# MCU_board_2.net
KiCad netlist of a schematic drawn in Altium Designer
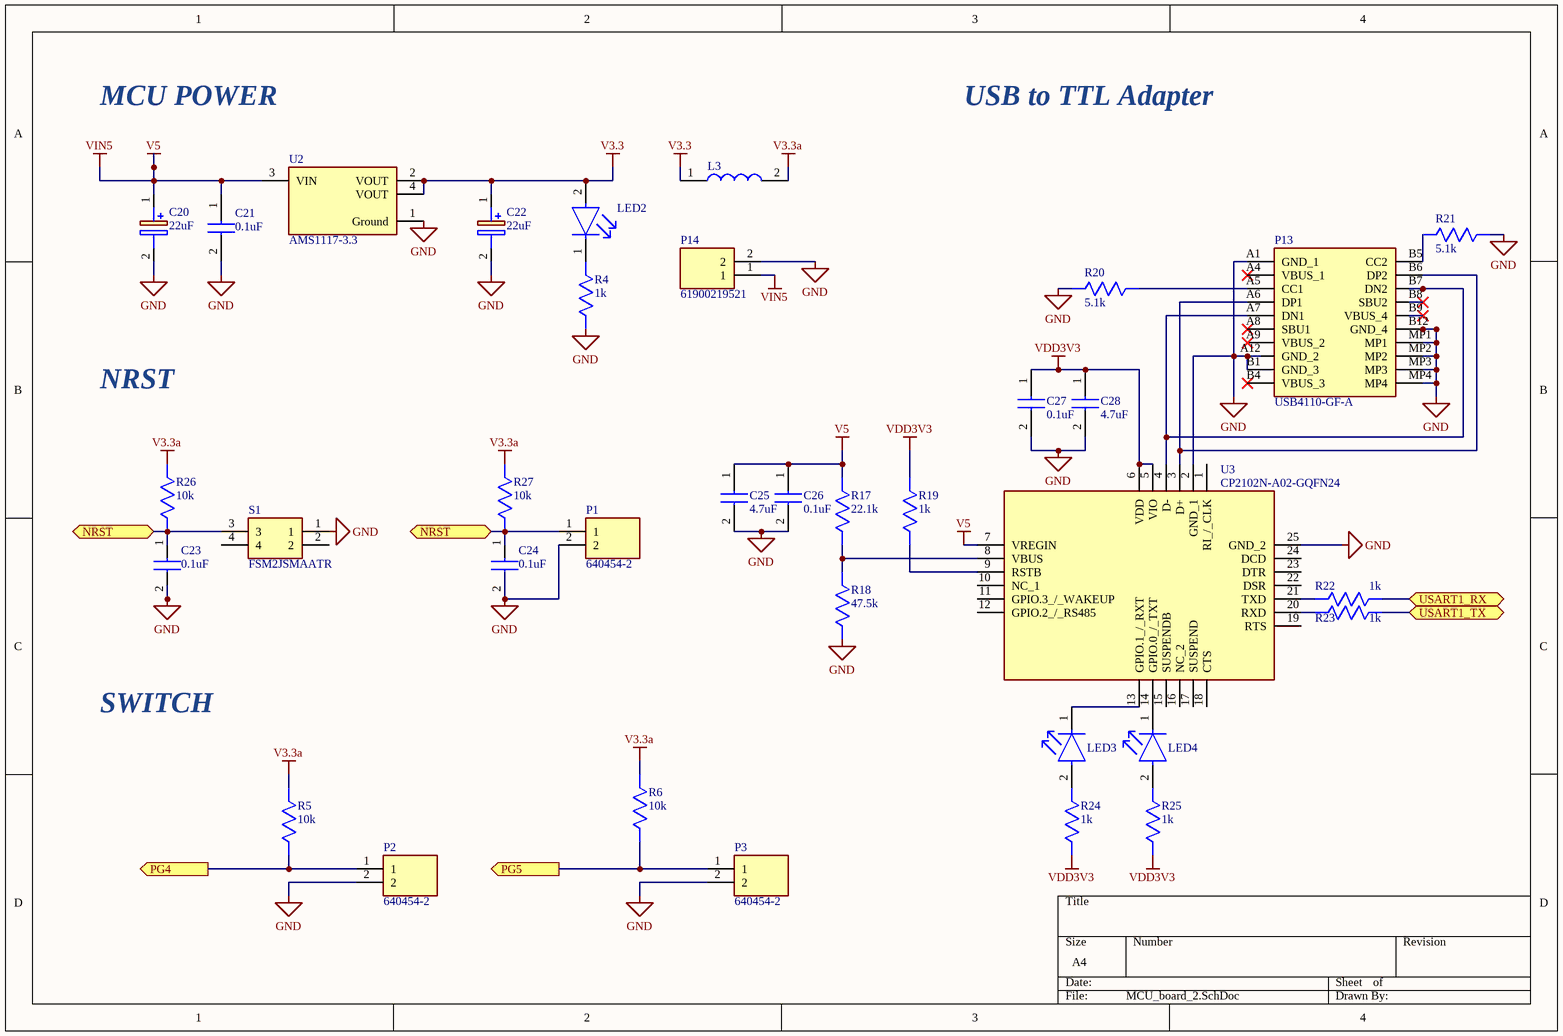
[diagram p0: MCU_board_2.SchDoc]

(export (version "E")
  (design (tool "Eeschema 10.0.6"))
  (components
    (comp (ref "C20")
      (value "22uF")
      (footprint "SamacSys:CAPPM6032X280N")
      (description "Capacitor Polarised")
      (fields
        (field (name "MANUFACTURER_PART_NUMBER") "TAJC226K025RNJ")
        (field (name "MOUSER PART NUMBER") "581-TAJC226K025R")
      )
      (libsource (lib "*") (part "TAJC226K025RNJ"))
    )
    (comp (ref "C21")
      (value "0.1uF")
      (footprint "SamacSys:C1608_Commercial")
      (description "Capacitor")
      (fields
        (field (name "MANUFACTURER_PART_NUMBER") "C1608X7R1H334K080AC")
        (field (name "MOUSER PART NUMBER") "810-C1608X7R1H334K")
      )
      (libsource (lib "*") (part "C1608X7R1H334K080AC"))
    )
    (comp (ref "C22")
      (value "22uF")
      (footprint "SamacSys:CAPPM6032X280N")
      (description "Capacitor Polarised")
      (fields
        (field (name "MANUFACTURER_PART_NUMBER") "TAJC226K025RNJ")
        (field (name "MOUSER PART NUMBER") "581-TAJC226K025R")
      )
      (libsource (lib "*") (part "TAJC226K025RNJ"))
    )
    (comp (ref "C23")
      (value "0.1uF")
      (footprint "SamacSys:C1608_Commercial")
      (description "Capacitor")
      (fields
        (field (name "MANUFACTURER_PART_NUMBER") "C1608X7R1H334K080AC")
        (field (name "MOUSER PART NUMBER") "810-C1608X7R1H334K")
      )
      (libsource (lib "*") (part "C1608X7R1H334K080AC"))
    )
    (comp (ref "C24")
      (value "0.1uF")
      (footprint "SamacSys:C1608_Commercial")
      (description "Capacitor")
      (fields
        (field (name "MANUFACTURER_PART_NUMBER") "C1608X7R1H334K080AC")
        (field (name "MOUSER PART NUMBER") "810-C1608X7R1H334K")
      )
      (libsource (lib "*") (part "C1608X7R1H334K080AC"))
    )
    (comp (ref "C25")
      (value "4.7uF")
      (footprint "SamacSys:CAPC1608X90N")
      (description "Capacitor")
      (fields
        (field (name "MANUFACTURER_PART_NUMBER") "GRM188R72A104MA35D")
        (field (name "MOUSER PART NUMBER") "81-GRM188R72A104MA5D")
      )
      (libsource (lib "*") (part "GRM188R72A104MA35D"))
    )
    (comp (ref "C26")
      (value "0.1uF")
      (footprint "SamacSys:CAPC1608X90N")
      (description "Capacitor")
      (fields
        (field (name "MANUFACTURER_PART_NUMBER") "GRM188R72A104MA35D")
        (field (name "MOUSER PART NUMBER") "81-GRM188R72A104MA5D")
      )
      (libsource (lib "*") (part "GRM188R72A104MA35D"))
    )
    (comp (ref "C27")
      (value "0.1uF")
      (footprint "SamacSys:CAPC1608X90N")
      (description "Capacitor")
      (fields
        (field (name "MANUFACTURER_PART_NUMBER") "GRM188R72A104MA35D")
        (field (name "MOUSER PART NUMBER") "81-GRM188R72A104MA5D")
      )
      (libsource (lib "*") (part "GRM188R72A104MA35D"))
    )
    (comp (ref "C28")
      (value "4.7uF")
      (footprint "SamacSys:CAPC1608X90N")
      (description "Capacitor")
      (fields
        (field (name "MANUFACTURER_PART_NUMBER") "GRM188R72A104MA35D")
        (field (name "MOUSER PART NUMBER") "81-GRM188R72A104MA5D")
      )
      (libsource (lib "*") (part "GRM188R72A104MA35D"))
    )
    (comp (ref "L3")
      (value "742792691")
      (footprint "SamacSys:LEDC1608X80N")
      (description "Inductor")
      (fields (field (name "MOUSER PART NUMBER") "710-742792691"))
      (libsource (lib "*") (part "742792691"))
    )
    (comp (ref "LED2")
      (value "150060RS75000")
      (footprint "FP-150060RS75000-MFG")
      (description "LED RED CLEAR 0603 SMD")
      (libsource (lib "Altium Content Vault") (part "8706943c75ba83719d021d2fdc84c58"))
    )
    (comp (ref "LED3")
      (value "150060RS75000")
      (footprint "FP-150060RS75000-MFG")
      (description "LED RED CLEAR 0603 SMD")
      (libsource (lib "Altium Content Vault") (part "8706943c75ba83719d021d2fdc84c58"))
    )
    (comp (ref "LED4")
      (value "150060RS75000")
      (footprint "FP-150060RS75000-MFG")
      (description "LED RED CLEAR 0603 SMD")
      (libsource (lib "Altium Content Vault") (part "8706943c75ba83719d021d2fdc84c58"))
    )
    (comp (ref "P1")
      (value "640454-2")
      (footprint "SamacSys:HDRV2W66P0X254_1X2_762X572X1003P")
      (description "Connector")
      (libsource (lib "*") (part "640454-2"))
    )
    (comp (ref "P2")
      (value "640454-2")
      (footprint "SamacSys:HDRV2W66P0X254_1X2_762X572X1003P")
      (description "Connector")
      (libsource (lib "SamacSys") (part "640454-2"))
    )
    (comp (ref "P3")
      (value "640454-2")
      (footprint "SamacSys:HDRV2W66P0X254_1X2_762X572X1003P")
      (description "Connector")
      (libsource (lib "SamacSys") (part "640454-2"))
    )
    (comp (ref "P13")
      (value "USB4110-GF-A")
      (footprint "SamacSys:USB4110GFA")
      (description "Connector")
      (fields (field (name "MOUSER PART NUMBER") "640-USB4110-GF-A"))
      (libsource (lib "SamacSys") (part "USB4110-GF-A"))
    )
    (comp (ref "P14")
      (value "61900219521")
      (footprint "SamacSys:SHDRRA2W64P0X254_1X2_508X1150X595P")
      (description "Connector")
      (fields (field (name "MOUSER PART NUMBER") "710-61900219521"))
      (libsource (lib "*") (part "61900219521"))
    )
    (comp (ref "R4")
      (value "1k")
      (footprint "SamacSys:RESC1608X55N")
      (description "Resistor")
      (fields (field (name "MANUFACTURER_PART_NUMBER") "CMP0603-FX-1003ELF"))
      (libsource (lib "SamacSys") (part "CMP0603-FX-1003ELF"))
    )
    (comp (ref "R5")
      (value "10k")
      (footprint "SamacSys:RESC1608X55N")
      (description "Resistor")
      (fields (field (name "MANUFACTURER_PART_NUMBER") "CMP0603-FX-1003ELF"))
      (libsource (lib "SamacSys") (part "CMP0603-FX-1003ELF"))
    )
    (comp (ref "R6")
      (value "10k")
      (footprint "SamacSys:RESC1608X55N")
      (description "Resistor")
      (fields (field (name "MANUFACTURER_PART_NUMBER") "CMP0603-FX-1003ELF"))
      (libsource (lib "SamacSys") (part "CMP0603-FX-1003ELF"))
    )
    (comp (ref "R17")
      (value "22.1k")
      (footprint "SamacSys:RESC1608X55N")
      (description "Resistor")
      (fields (field (name "MANUFACTURER_PART_NUMBER") "CMP0603-FX-1003ELF"))
      (libsource (lib "SamacSys") (part "CMP0603-FX-1003ELF"))
    )
    (comp (ref "R18")
      (value "47.5k")
      (footprint "SamacSys:RESC1608X55N")
      (description "Resistor")
      (fields (field (name "MANUFACTURER_PART_NUMBER") "CMP0603-FX-1003ELF"))
      (libsource (lib "SamacSys") (part "CMP0603-FX-1003ELF"))
    )
    (comp (ref "R19")
      (value "1k")
      (footprint "SamacSys:RESC1608X55N")
      (description "Resistor")
      (fields (field (name "MANUFACTURER_PART_NUMBER") "CMP0603-FX-1003ELF"))
      (libsource (lib "SamacSys") (part "CMP0603-FX-1003ELF"))
    )
    (comp (ref "R20")
      (value "5.1k")
      (footprint "SamacSys:RESC1608X55N")
      (description "Resistor")
      (fields (field (name "MANUFACTURER_PART_NUMBER") "CMP0603-FX-1003ELF"))
      (libsource (lib "SamacSys") (part "CMP0603-FX-1003ELF"))
    )
    (comp (ref "R21")
      (value "5.1k")
      (footprint "SamacSys:RESC1608X55N")
      (description "Resistor")
      (fields (field (name "MANUFACTURER_PART_NUMBER") "CMP0603-FX-1003ELF"))
      (libsource (lib "SamacSys") (part "CMP0603-FX-1003ELF"))
    )
    (comp (ref "R22")
      (value "1k")
      (footprint "SamacSys:RESC1608X55N")
      (description "Resistor")
      (fields (field (name "MANUFACTURER_PART_NUMBER") "CMP0603-FX-1003ELF"))
      (libsource (lib "SamacSys") (part "CMP0603-FX-1003ELF"))
    )
    (comp (ref "R23")
      (value "1k")
      (footprint "SamacSys:RESC1608X55N")
      (description "Resistor")
      (fields (field (name "MANUFACTURER_PART_NUMBER") "CMP0603-FX-1003ELF"))
      (libsource (lib "SamacSys") (part "CMP0603-FX-1003ELF"))
    )
    (comp (ref "R24")
      (value "1k")
      (footprint "SamacSys:RESC1608X55N")
      (description "Resistor")
      (fields (field (name "MANUFACTURER_PART_NUMBER") "CMP0603-FX-1003ELF"))
      (libsource (lib "SamacSys") (part "CMP0603-FX-1003ELF"))
    )
    (comp (ref "R25")
      (value "1k")
      (footprint "SamacSys:RESC1608X55N")
      (description "Resistor")
      (fields (field (name "MANUFACTURER_PART_NUMBER") "CMP0603-FX-1003ELF"))
      (libsource (lib "SamacSys") (part "CMP0603-FX-1003ELF"))
    )
    (comp (ref "R26")
      (value "10k")
      (footprint "SamacSys:RESC1608X55N")
      (description "Resistor")
      (fields (field (name "MANUFACTURER_PART_NUMBER") "CMP0603-FX-1003ELF"))
      (libsource (lib "SamacSys") (part "CMP0603-FX-1003ELF"))
    )
    (comp (ref "R27")
      (value "10k")
      (footprint "SamacSys:RESC1608X55N")
      (description "Resistor")
      (fields (field (name "MANUFACTURER_PART_NUMBER") "CMP0603-FX-1003ELF"))
      (libsource (lib "SamacSys") (part "CMP0603-FX-1003ELF"))
    )
    (comp (ref "S1")
      (value "FSM2JSMAATR")
      (footprint "SamacSys:FSM2J_1")
      (description "Switch")
      (libsource (lib "SamacSys") (part "FSM2JSMAATR"))
    )
    (comp (ref "U2")
      (value "AMS1117-3.3")
      (footprint "FP-AMS1117-IPC_C")
      (description "LDO Voltage Regulators 1A, 3.3V")
      (fields
        (field (name "OCTOPART") "https://octopart.com/ams1117-3.3-advanced+monolithic+systems-25899300")
        (field (name "MANUFACTURER") "Advanced Monolithic Systems")
      )
      (libsource (lib "Altium Content Vault") (part "8bdbb5f8e77002000e30dd2845d0354"))
    )
    (comp (ref "U3")
      (value "CP2102N-A02-GQFN24")
      (footprint "SamacSys:QFN50P400X400X80-25N-D")
      (description "Integrated Circuit")
      (fields (field (name "MOUSER PART NUMBER") "634-CP2102NA02GQFN24"))
      (libsource (lib "*") (part "CP2102N-A02-GQFN24"))
    )
  )
  (nets
    (net (code "1") (name "/NRST") (class "Default")
      (node (ref "C23") (pin "1") (pinfunction "1_1") (pintype "passive"))
      (node (ref "C24") (pin "1") (pinfunction "1_1") (pintype "passive"))
      (node (ref "P1") (pin "1") (pinfunction "1_1") (pintype "passive"))
      (node (ref "R26") (pin "1") (pinfunction "1_1") (pintype "passive"))
      (node (ref "R27") (pin "1") (pinfunction "1_1") (pintype "passive"))
      (node (ref "S1") (pin "3") (pinfunction "3_3") (pintype "passive"))
    )
    (net (code "2") (name "/PG4") (class "Default")
      (node (ref "P2") (pin "1") (pinfunction "1_1") (pintype "passive"))
      (node (ref "R5") (pin "1") (pinfunction "1_1") (pintype "passive"))
    )
    (net (code "3") (name "/PG5") (class "Default")
      (node (ref "P3") (pin "1") (pinfunction "1_1") (pintype "passive"))
      (node (ref "R6") (pin "1") (pinfunction "1_1") (pintype "passive"))
    )
    (net (code "4") (name "/USART1_RX") (class "Default")
      (node (ref "R22") (pin "2") (pinfunction "2_2") (pintype "passive"))
    )
    (net (code "5") (name "/USART1_TX") (class "Default")
      (node (ref "R23") (pin "2") (pinfunction "2_2") (pintype "passive"))
    )
    (net (code "6") (name "GND") (class "Default")
      (node (ref "C20") (pin "2") (pinfunction "-_2") (pintype "passive"))
      (node (ref "C21") (pin "2") (pinfunction "2_2") (pintype "passive"))
      (node (ref "C22") (pin "2") (pinfunction "-_2") (pintype "passive"))
      (node (ref "C23") (pin "2") (pinfunction "2_2") (pintype "passive"))
      (node (ref "C24") (pin "2") (pinfunction "2_2") (pintype "passive"))
      (node (ref "C25") (pin "2") (pinfunction "2_2") (pintype "passive"))
      (node (ref "C26") (pin "2") (pinfunction "2_2") (pintype "passive"))
      (node (ref "C27") (pin "2") (pinfunction "2_2") (pintype "passive"))
      (node (ref "C28") (pin "2") (pinfunction "2_2") (pintype "passive"))
      (node (ref "P1") (pin "2") (pinfunction "2_2") (pintype "passive"))
      (node (ref "P13") (pin "A1") (pinfunction "GND_1_A1") (pintype "passive"))
      (node (ref "P13") (pin "A12") (pinfunction "GND_2_A12") (pintype "passive"))
      (node (ref "P13") (pin "B1") (pinfunction "GND_3_B1") (pintype "passive"))
      (node (ref "P13") (pin "B12") (pinfunction "GND_4_B12") (pintype "passive"))
      (node (ref "P13") (pin "MP1") (pinfunction "MP1_MP1") (pintype "passive"))
      (node (ref "P13") (pin "MP2") (pinfunction "MP2_MP2") (pintype "passive"))
      (node (ref "P13") (pin "MP3") (pinfunction "MP3_MP3") (pintype "passive"))
      (node (ref "P13") (pin "MP4") (pinfunction "MP4_MP4") (pintype "passive"))
      (node (ref "P14") (pin "2") (pinfunction "2_2") (pintype "passive"))
      (node (ref "P2") (pin "2") (pinfunction "2_2") (pintype "passive"))
      (node (ref "P3") (pin "2") (pinfunction "2_2") (pintype "passive"))
      (node (ref "R18") (pin "2") (pinfunction "2_2") (pintype "passive"))
      (node (ref "R20") (pin "2") (pinfunction "2_2") (pintype "passive"))
      (node (ref "R21") (pin "2") (pinfunction "2_2") (pintype "passive"))
      (node (ref "R4") (pin "2") (pinfunction "2_2") (pintype "passive"))
      (node (ref "S1") (pin "1") (pinfunction "1_1") (pintype "passive"))
      (node (ref "U2") (pin "1") (pinfunction "Ground_1") (pintype "power_in"))
      (node (ref "U3") (pin "2") (pinfunction "GND_1_2") (pintype "passive"))
      (node (ref "U3") (pin "25") (pinfunction "GND_2_25") (pintype "passive"))
    )
    (net (code "7") (name "Net-(LED2-C)") (class "Default")
      (node (ref "LED2") (pin "1") (pinfunction "C_1") (pintype "passive"))
      (node (ref "R4") (pin "1") (pinfunction "1_1") (pintype "passive"))
    )
    (net (code "8") (name "Net-(LED3-A)") (class "Default")
      (node (ref "LED3") (pin "2") (pinfunction "A_2") (pintype "passive"))
      (node (ref "R24") (pin "1") (pinfunction "1_1") (pintype "passive"))
    )
    (net (code "9") (name "Net-(LED3-C)") (class "Default")
      (node (ref "LED3") (pin "1") (pinfunction "C_1") (pintype "passive"))
      (node (ref "U3") (pin "13") (pinfunction "GPIO.1_/_RXT_13") (pintype "passive"))
    )
    (net (code "10") (name "Net-(LED4-A)") (class "Default")
      (node (ref "LED4") (pin "2") (pinfunction "A_2") (pintype "passive"))
      (node (ref "R25") (pin "1") (pinfunction "1_1") (pintype "passive"))
    )
    (net (code "11") (name "Net-(LED4-C)") (class "Default")
      (node (ref "LED4") (pin "1") (pinfunction "C_1") (pintype "passive"))
      (node (ref "U3") (pin "14") (pinfunction "GPIO.0_/_TXT_14") (pintype "passive"))
    )
    (net (code "12") (name "Net-(P13-CC1)") (class "Default")
      (node (ref "P13") (pin "A5") (pinfunction "CC1_A5") (pintype "passive"))
      (node (ref "R20") (pin "1") (pinfunction "1_1") (pintype "passive"))
    )
    (net (code "13") (name "Net-(P13-CC2)") (class "Default")
      (node (ref "P13") (pin "B5") (pinfunction "CC2_B5") (pintype "passive"))
      (node (ref "R21") (pin "1") (pinfunction "1_1") (pintype "passive"))
    )
    (net (code "14") (name "Net-(P13-DN1)") (class "Default")
      (node (ref "P13") (pin "A7") (pinfunction "DN1_A7") (pintype "passive"))
      (node (ref "P13") (pin "B7") (pinfunction "DN2_B7") (pintype "passive"))
      (node (ref "U3") (pin "4") (pinfunction "D-_4") (pintype "passive"))
    )
    (net (code "15") (name "Net-(P13-DP1)") (class "Default")
      (node (ref "P13") (pin "A6") (pinfunction "DP1_A6") (pintype "passive"))
      (node (ref "P13") (pin "B6") (pinfunction "DP2_B6") (pintype "passive"))
      (node (ref "U3") (pin "3") (pinfunction "D+_3") (pintype "passive"))
    )
    (net (code "16") (name "Net-(U3-RSTB)") (class "Default")
      (node (ref "R19") (pin "2") (pinfunction "2_2") (pintype "passive"))
      (node (ref "U3") (pin "9") (pinfunction "RSTB_9") (pintype "passive"))
    )
    (net (code "17") (name "Net-(U3-RXD)") (class "Default")
      (node (ref "R23") (pin "1") (pinfunction "1_1") (pintype "passive"))
      (node (ref "U3") (pin "20") (pinfunction "RXD_20") (pintype "passive"))
    )
    (net (code "18") (name "Net-(U3-TXD)") (class "Default")
      (node (ref "R22") (pin "1") (pinfunction "1_1") (pintype "passive"))
      (node (ref "U3") (pin "21") (pinfunction "TXD_21") (pintype "passive"))
    )
    (net (code "19") (name "Net-(U3-VBUS)") (class "Default")
      (node (ref "R17") (pin "2") (pinfunction "2_2") (pintype "passive"))
      (node (ref "R18") (pin "1") (pinfunction "1_1") (pintype "passive"))
      (node (ref "U3") (pin "8") (pinfunction "VBUS_8") (pintype "passive"))
    )
    (net (code "20") (name "V3.3") (class "Default")
      (node (ref "C22") (pin "1") (pinfunction "+_1") (pintype "passive"))
      (node (ref "L3") (pin "1") (pinfunction "1_1") (pintype "passive"))
      (node (ref "LED2") (pin "2") (pinfunction "A_2") (pintype "passive"))
      (node (ref "U2") (pin "2") (pinfunction "VOUT_2") (pintype "passive"))
      (node (ref "U2") (pin "4") (pinfunction "VOUT_4") (pintype "passive"))
    )
    (net (code "21") (name "V3.3a") (class "Default")
      (node (ref "L3") (pin "2") (pinfunction "2_2") (pintype "passive"))
      (node (ref "R26") (pin "2") (pinfunction "2_2") (pintype "passive"))
      (node (ref "R27") (pin "2") (pinfunction "2_2") (pintype "passive"))
      (node (ref "R5") (pin "2") (pinfunction "2_2") (pintype "passive"))
      (node (ref "R6") (pin "2") (pinfunction "2_2") (pintype "passive"))
    )
    (net (code "22") (name "V5") (class "Default")
      (node (ref "C20") (pin "1") (pinfunction "+_1") (pintype "passive"))
      (node (ref "C21") (pin "1") (pinfunction "1_1") (pintype "passive"))
      (node (ref "C25") (pin "1") (pinfunction "1_1") (pintype "passive"))
      (node (ref "C26") (pin "1") (pinfunction "1_1") (pintype "passive"))
      (node (ref "P14") (pin "1") (pinfunction "1_1") (pintype "passive"))
      (node (ref "R17") (pin "1") (pinfunction "1_1") (pintype "passive"))
      (node (ref "U2") (pin "3") (pinfunction "VIN_3") (pintype "power_in"))
      (node (ref "U3") (pin "7") (pinfunction "VREGIN_7") (pintype "passive"))
    )
    (net (code "23") (name "VDD3V3") (class "Default")
      (node (ref "C27") (pin "1") (pinfunction "1_1") (pintype "passive"))
      (node (ref "C28") (pin "1") (pinfunction "1_1") (pintype "passive"))
      (node (ref "R19") (pin "1") (pinfunction "1_1") (pintype "passive"))
      (node (ref "R24") (pin "2") (pinfunction "2_2") (pintype "passive"))
      (node (ref "R25") (pin "2") (pinfunction "2_2") (pintype "passive"))
      (node (ref "U3") (pin "5") (pinfunction "VIO_5") (pintype "passive"))
      (node (ref "U3") (pin "6") (pinfunction "VDD_6") (pintype "passive"))
    )
    (net (code "24") (name "unconnected-(P13-SBU1-PadA8)") (class "Default")
      (node (ref "P13") (pin "A8") (pinfunction "SBU1_A8") (pintype "passive+no_connect"))
    )
    (net (code "25") (name "unconnected-(P13-SBU2-PadB8)") (class "Default")
      (node (ref "P13") (pin "B8") (pinfunction "SBU2_B8") (pintype "passive+no_connect"))
    )
    (net (code "26") (name "unconnected-(P13-VBUS_1-PadA4)") (class "Default")
      (node (ref "P13") (pin "A4") (pinfunction "VBUS_1_A4") (pintype "passive+no_connect"))
    )
    (net (code "27") (name "unconnected-(P13-VBUS_2-PadA9)") (class "Default")
      (node (ref "P13") (pin "A9") (pinfunction "VBUS_2_A9") (pintype "passive+no_connect"))
    )
    (net (code "28") (name "unconnected-(P13-VBUS_3-PadB4)") (class "Default")
      (node (ref "P13") (pin "B4") (pinfunction "VBUS_3_B4") (pintype "passive+no_connect"))
    )
    (net (code "29") (name "unconnected-(P13-VBUS_4-PadB9)") (class "Default")
      (node (ref "P13") (pin "B9") (pinfunction "VBUS_4_B9") (pintype "passive+no_connect"))
    )
    (net (code "30") (name "unconnected-(S1-Pad2)") (class "Default")
      (node (ref "S1") (pin "2") (pinfunction "2_2") (pintype "passive"))
    )
    (net (code "31") (name "unconnected-(S1-Pad4)") (class "Default")
      (node (ref "S1") (pin "4") (pinfunction "4_4") (pintype "passive"))
    )
    (net (code "32") (name "unconnected-(U3-CTS-Pad18)") (class "Default")
      (node (ref "U3") (pin "18") (pinfunction "CTS_18") (pintype "passive"))
    )
    (net (code "33") (name "unconnected-(U3-DCD-Pad24)") (class "Default")
      (node (ref "U3") (pin "24") (pinfunction "DCD_24") (pintype "passive"))
    )
    (net (code "34") (name "unconnected-(U3-DSR-Pad22)") (class "Default")
      (node (ref "U3") (pin "22") (pinfunction "DSR_22") (pintype "passive"))
    )
    (net (code "35") (name "unconnected-(U3-DTR-Pad23)") (class "Default")
      (node (ref "U3") (pin "23") (pinfunction "DTR_23") (pintype "passive"))
    )
    (net (code "36") (name "unconnected-(U3-GPIO.2_{slash}_RS485-Pad12)") (class "Default")
      (node (ref "U3") (pin "12") (pinfunction "GPIO.2_/_RS485_12") (pintype "passive"))
    )
    (net (code "37") (name "unconnected-(U3-GPIO.3_{slash}_WAKEUP-Pad11)") (class "Default")
      (node (ref "U3") (pin "11") (pinfunction "GPIO.3_/_WAKEUP_11") (pintype "passive"))
    )
    (net (code "38") (name "unconnected-(U3-NC_1-Pad10)") (class "Default")
      (node (ref "U3") (pin "10") (pinfunction "NC_1_10") (pintype "passive"))
    )
    (net (code "39") (name "unconnected-(U3-NC_2-Pad16)") (class "Default")
      (node (ref "U3") (pin "16") (pinfunction "NC_2_16") (pintype "passive"))
    )
    (net (code "40") (name "unconnected-(U3-RI_{slash}_CLK-Pad1)") (class "Default")
      (node (ref "U3") (pin "1") (pinfunction "RI_/_CLK_1") (pintype "passive"))
    )
    (net (code "41") (name "unconnected-(U3-RTS-Pad19)") (class "Default")
      (node (ref "U3") (pin "19") (pinfunction "RTS_19") (pintype "passive"))
    )
    (net (code "42") (name "unconnected-(U3-SUSPEND-Pad17)") (class "Default")
      (node (ref "U3") (pin "17") (pinfunction "SUSPEND_17") (pintype "passive"))
    )
    (net (code "43") (name "unconnected-(U3-SUSPENDB-Pad15)") (class "Default")
      (node (ref "U3") (pin "15") (pinfunction "SUSPENDB_15") (pintype "passive"))
    )
  )
)
